# Sheet1.net
KiCad netlist of a schematic drawn in Altium Designer
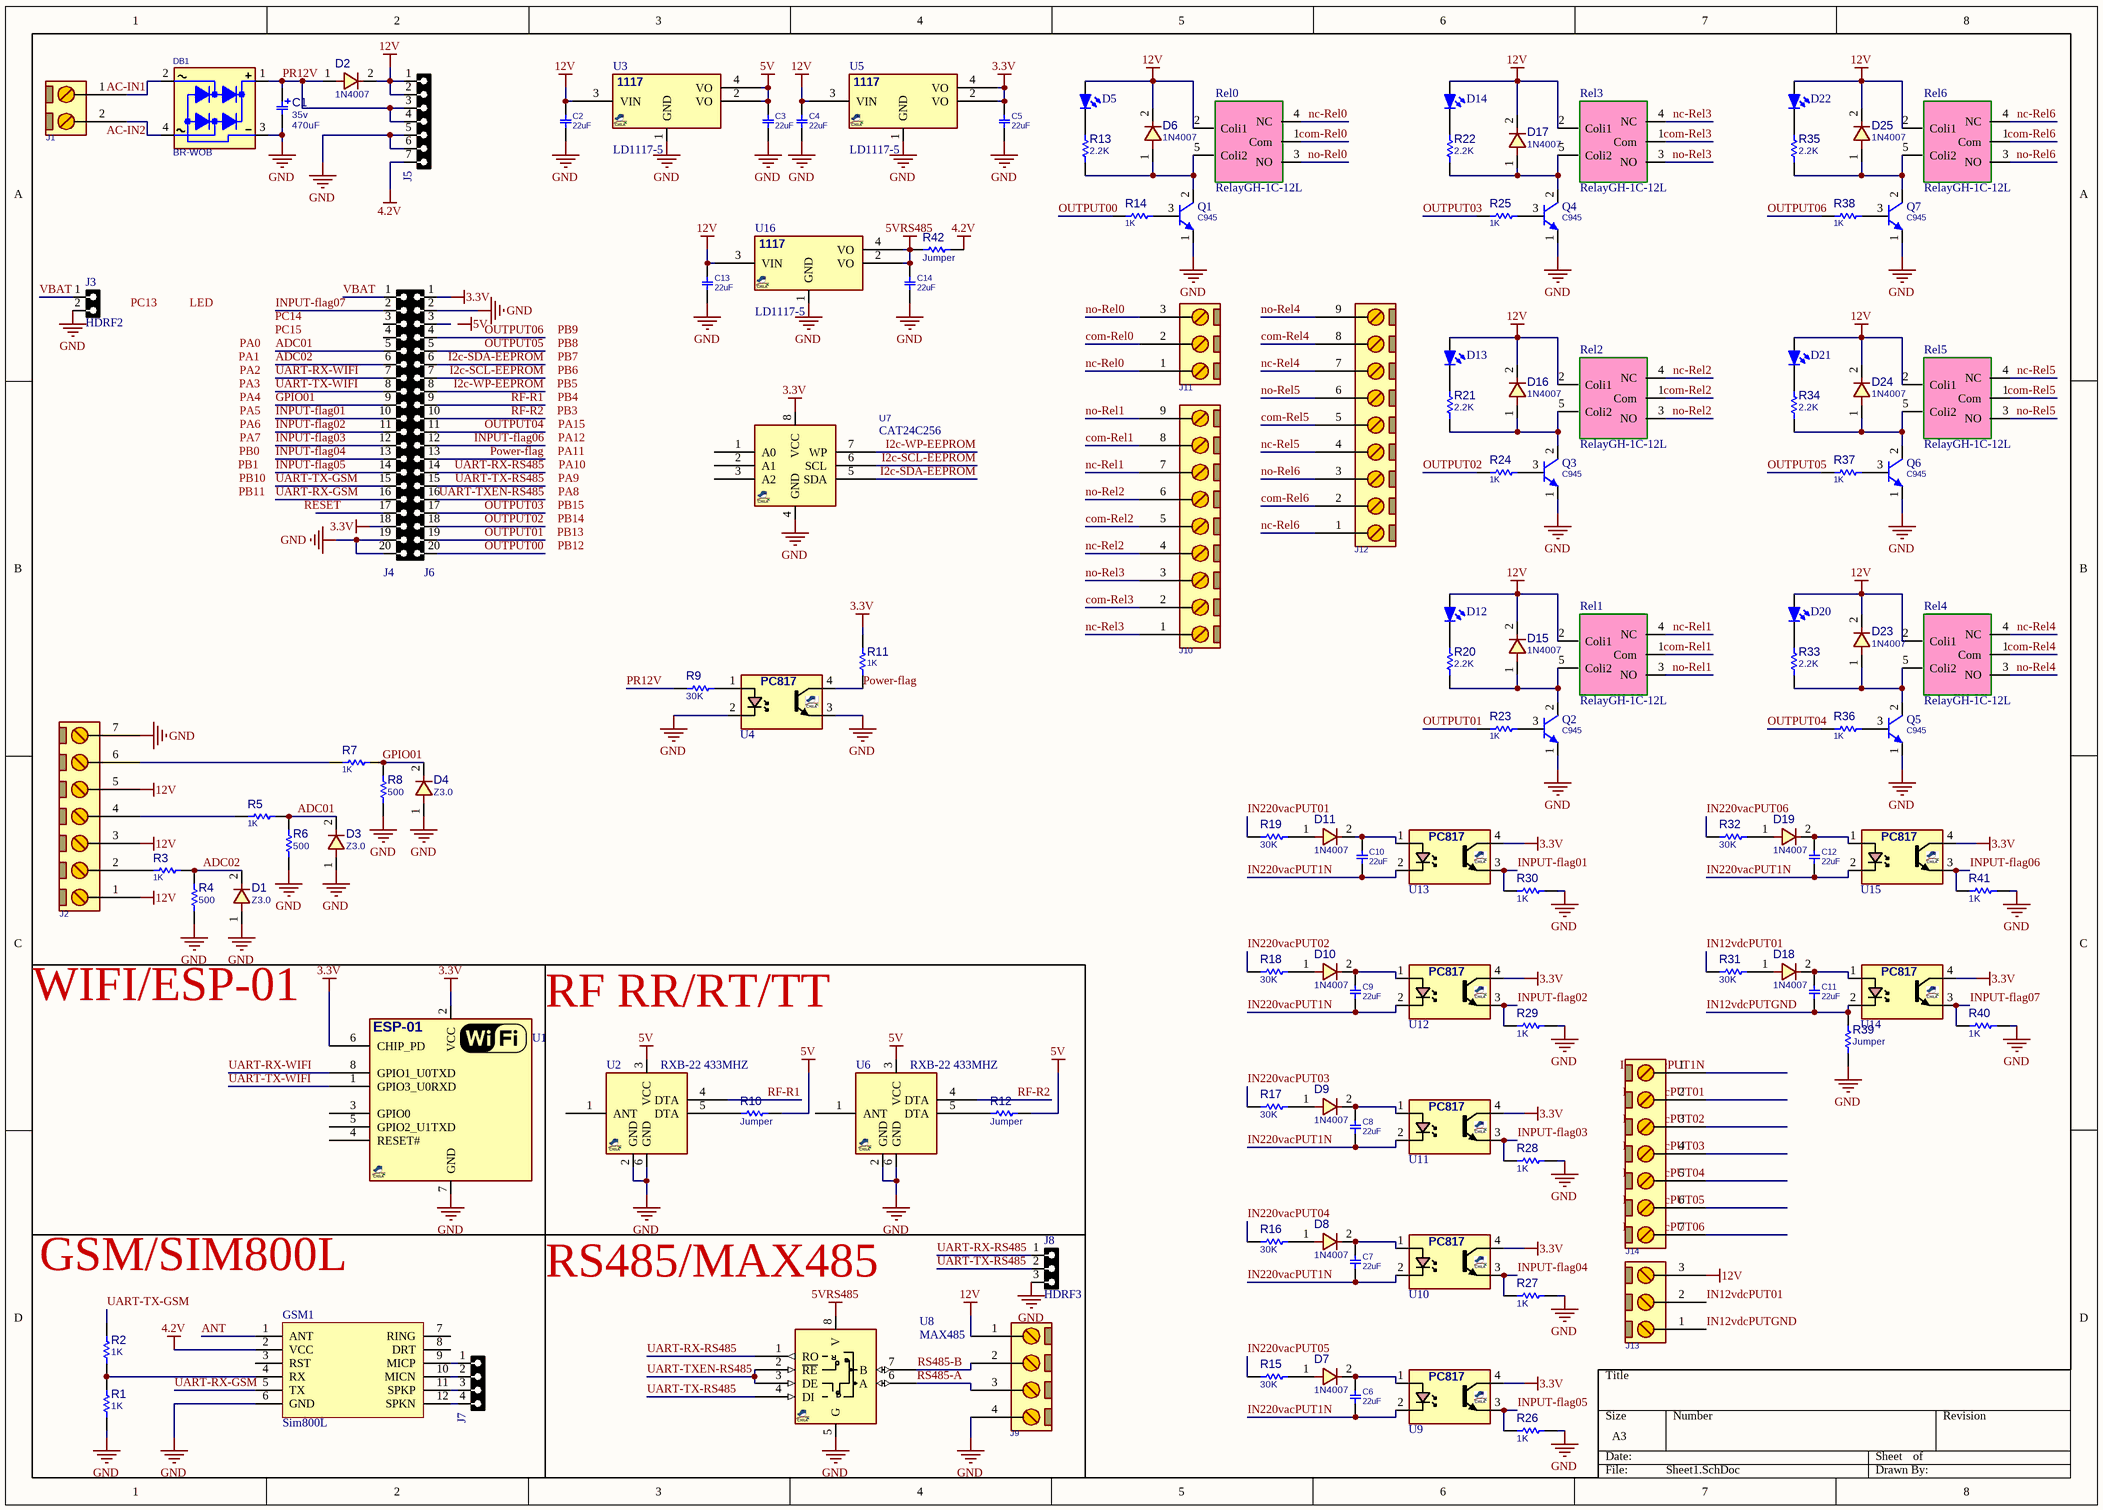
[diagram p0: Sheet1.SchDoc]

(export (version "E")
  (design (tool "Eeschema 10.0.6"))
  (components
    (comp (ref "C1")
      (value "470uF")
      (footprint "C_EL_10X16")
      (description "CAP, THD, ELEC,")
      (fields
        (field (name "MANF_P#") "MANF_PART#")
        (field (name "MANF") "MANF")
        (field (name "PARAM2") "35v")
      )
      (libsource (lib "passive_thd") (part "CAP_THD_EL_470uF_35v"))
    )
    (comp (ref "C2")
      (value "22uF")
      (footprint "C0805")
      (description "CAP, MLCC, X5R 10uF 10% 25V 0805")
      (fields (field (name "MANF_P#") "TMK212BBJ106MG") (field (name "MANF") "Taiyo Yuden"))
      (libsource (lib "mlcc_smd_passive") (part "CAP_SMD_MLCC_10u25V"))
    )
    (comp (ref "C3")
      (value "22uF")
      (footprint "C0805")
      (description "CAP, MLCC, X5R 10uF 10% 25V 0805")
      (fields (field (name "MANF_P#") "TMK212BBJ106MG") (field (name "MANF") "Taiyo Yuden"))
      (libsource (lib "mlcc_smd_passive") (part "CAP_SMD_MLCC_10u25V"))
    )
    (comp (ref "C4")
      (value "22uF")
      (footprint "C0805")
      (description "CAP, MLCC, X5R 10uF 10% 25V 0805")
      (fields (field (name "MANF_P#") "TMK212BBJ106MG") (field (name "MANF") "Taiyo Yuden"))
      (libsource (lib "mlcc_smd_passive") (part "CAP_SMD_MLCC_10u25V"))
    )
    (comp (ref "C5")
      (value "22uF")
      (footprint "C0805")
      (description "CAP, MLCC, X5R 10uF 10% 25V 0805")
      (fields (field (name "MANF_P#") "TMK212BBJ106MG") (field (name "MANF") "Taiyo Yuden"))
      (libsource (lib "mlcc_smd_passive") (part "CAP_SMD_MLCC_10u25V"))
    )
    (comp (ref "C6")
      (value "22uF")
      (footprint "C0805")
      (description "CAP, MLCC, X5R 10uF 10% 25V 0805")
      (fields (field (name "MANF_P#") "TMK212BBJ106MG") (field (name "MANF") "Taiyo Yuden"))
      (libsource (lib "mlcc_smd_passive") (part "CAP_SMD_MLCC_10u25V"))
    )
    (comp (ref "C7")
      (value "22uF")
      (footprint "C0805")
      (description "CAP, MLCC, X5R 10uF 10% 25V 0805")
      (fields (field (name "MANF_P#") "TMK212BBJ106MG") (field (name "MANF") "Taiyo Yuden"))
      (libsource (lib "mlcc_smd_passive") (part "CAP_SMD_MLCC_10u25V"))
    )
    (comp (ref "C8")
      (value "22uF")
      (footprint "C0805")
      (description "CAP, MLCC, X5R 10uF 10% 25V 0805")
      (fields (field (name "MANF_P#") "TMK212BBJ106MG") (field (name "MANF") "Taiyo Yuden"))
      (libsource (lib "mlcc_smd_passive") (part "CAP_SMD_MLCC_10u25V"))
    )
    (comp (ref "C9")
      (value "22uF")
      (footprint "C0805")
      (description "CAP, MLCC, X5R 10uF 10% 25V 0805")
      (fields (field (name "MANF_P#") "TMK212BBJ106MG") (field (name "MANF") "Taiyo Yuden"))
      (libsource (lib "mlcc_smd_passive") (part "CAP_SMD_MLCC_10u25V"))
    )
    (comp (ref "C10")
      (value "22uF")
      (footprint "C0805")
      (description "CAP, MLCC, X5R 10uF 10% 25V 0805")
      (fields (field (name "MANF_P#") "TMK212BBJ106MG") (field (name "MANF") "Taiyo Yuden"))
      (libsource (lib "mlcc_smd_passive") (part "CAP_SMD_MLCC_10u25V"))
    )
    (comp (ref "C11")
      (value "22uF")
      (footprint "C0805")
      (description "CAP, MLCC, X5R 10uF 10% 25V 0805")
      (fields (field (name "MANF_P#") "TMK212BBJ106MG") (field (name "MANF") "Taiyo Yuden"))
      (libsource (lib "mlcc_smd_passive") (part "CAP_SMD_MLCC_10u25V"))
    )
    (comp (ref "C12")
      (value "22uF")
      (footprint "C0805")
      (description "CAP, MLCC, X5R 10uF 10% 25V 0805")
      (fields (field (name "MANF_P#") "TMK212BBJ106MG") (field (name "MANF") "Taiyo Yuden"))
      (libsource (lib "mlcc_smd_passive") (part "CAP_SMD_MLCC_10u25V"))
    )
    (comp (ref "C13")
      (value "22uF")
      (footprint "C0805")
      (description "CAP, MLCC, X5R 10uF 10% 25V 0805")
      (fields (field (name "MANF_P#") "TMK212BBJ106MG") (field (name "MANF") "Taiyo Yuden"))
      (libsource (lib "mlcc_smd_passive") (part "CAP_SMD_MLCC_10u25V"))
    )
    (comp (ref "C14")
      (value "22uF")
      (footprint "C0805")
      (description "CAP, MLCC, X5R 10uF 10% 25V 0805")
      (fields (field (name "MANF_P#") "TMK212BBJ106MG") (field (name "MANF") "Taiyo Yuden"))
      (libsource (lib "mlcc_smd_passive") (part "CAP_SMD_MLCC_10u25V"))
    )
    (comp (ref "D1")
      (value "Z3.0")
      (footprint "D_SOD80")
      (description "DIODE, FAST SWTICHING, 0.3A, 0.5W")
      (fields (field (name "MANF") "MANF") (field (name "MANF_P#") "1N4148"))
      (libsource (lib "altium-import") (part "root_1_DIODE_SMD_1N4148_SOD80_"))
    )
    (comp (ref "D2")
      (value "1N4007")
      (footprint "D_SMA")
      (description "DIODE, GENERAL PURPOSE, 1000V/1A")
      (fields (field (name "MANF") "Kingtronics") (field (name "MANF_P#") "M7"))
      (libsource (lib "diode") (part "DIODE_SMD_1N4007"))
    )
    (comp (ref "D3")
      (value "Z3.0")
      (footprint "D_SOD80")
      (description "DIODE, FAST SWTICHING, 0.3A, 0.5W")
      (fields (field (name "MANF") "MANF") (field (name "MANF_P#") "1N4148"))
      (libsource (lib "altium-import") (part "root_1_DIODE_SMD_1N4148_SOD80_"))
    )
    (comp (ref "D4")
      (value "Z3.0")
      (footprint "D_SOD80")
      (description "DIODE, FAST SWTICHING, 0.3A, 0.5W")
      (fields (field (name "MANF") "MANF") (field (name "MANF_P#") "1N4148"))
      (libsource (lib "altium-import") (part "root_1_DIODE_SMD_1N4148_SOD80_"))
    )
    (comp (ref "D5")
      (value "~")
      (footprint "0805 LED")
      (description "Led")
      (fields (field (name "PUBLISHER") "Altium Limited"))
      (libsource (lib "Sajad_Altium_Library") (part "LED"))
    )
    (comp (ref "D6")
      (value "1N4007")
      (footprint "D_SMA")
      (description "DIODE, GENERAL PURPOSE, 1000V/1A")
      (fields (field (name "MANF") "Kingtronics") (field (name "MANF_P#") "M7"))
      (libsource (lib "diode") (part "DIODE_SMD_1N4007"))
    )
    (comp (ref "D7")
      (value "1N4007")
      (footprint "D_SMA")
      (description "DIODE, GENERAL PURPOSE, 1000V/1A")
      (fields (field (name "MANF") "Kingtronics") (field (name "MANF_P#") "M7"))
      (libsource (lib "diode") (part "DIODE_SMD_1N4007"))
    )
    (comp (ref "D8")
      (value "1N4007")
      (footprint "D_SMA")
      (description "DIODE, GENERAL PURPOSE, 1000V/1A")
      (fields (field (name "MANF") "Kingtronics") (field (name "MANF_P#") "M7"))
      (libsource (lib "diode") (part "DIODE_SMD_1N4007"))
    )
    (comp (ref "D9")
      (value "1N4007")
      (footprint "D_SMA")
      (description "DIODE, GENERAL PURPOSE, 1000V/1A")
      (fields (field (name "MANF") "Kingtronics") (field (name "MANF_P#") "M7"))
      (libsource (lib "diode") (part "DIODE_SMD_1N4007"))
    )
    (comp (ref "D10")
      (value "1N4007")
      (footprint "D_SMA")
      (description "DIODE, GENERAL PURPOSE, 1000V/1A")
      (fields (field (name "MANF") "Kingtronics") (field (name "MANF_P#") "M7"))
      (libsource (lib "diode") (part "DIODE_SMD_1N4007"))
    )
    (comp (ref "D11")
      (value "1N4007")
      (footprint "D_SMA")
      (description "DIODE, GENERAL PURPOSE, 1000V/1A")
      (fields (field (name "MANF") "Kingtronics") (field (name "MANF_P#") "M7"))
      (libsource (lib "diode") (part "DIODE_SMD_1N4007"))
    )
    (comp (ref "D12")
      (value "~")
      (footprint "0805 LED")
      (description "Led")
      (fields (field (name "PUBLISHER") "Altium Limited"))
      (libsource (lib "Sajad_Altium_Library") (part "LED"))
    )
    (comp (ref "D13")
      (value "~")
      (footprint "0805 LED")
      (description "Led")
      (fields (field (name "PUBLISHER") "Altium Limited"))
      (libsource (lib "Sajad_Altium_Library") (part "LED"))
    )
    (comp (ref "D14")
      (value "~")
      (footprint "0805 LED")
      (description "Led")
      (fields (field (name "PUBLISHER") "Altium Limited"))
      (libsource (lib "Sajad_Altium_Library") (part "LED"))
    )
    (comp (ref "D15")
      (value "1N4007")
      (footprint "D_SMA")
      (description "DIODE, GENERAL PURPOSE, 1000V/1A")
      (fields (field (name "MANF") "Kingtronics") (field (name "MANF_P#") "M7"))
      (libsource (lib "diode") (part "DIODE_SMD_1N4007"))
    )
    (comp (ref "D16")
      (value "1N4007")
      (footprint "D_SMA")
      (description "DIODE, GENERAL PURPOSE, 1000V/1A")
      (fields (field (name "MANF") "Kingtronics") (field (name "MANF_P#") "M7"))
      (libsource (lib "diode") (part "DIODE_SMD_1N4007"))
    )
    (comp (ref "D17")
      (value "1N4007")
      (footprint "D_SMA")
      (description "DIODE, GENERAL PURPOSE, 1000V/1A")
      (fields (field (name "MANF") "Kingtronics") (field (name "MANF_P#") "M7"))
      (libsource (lib "diode") (part "DIODE_SMD_1N4007"))
    )
    (comp (ref "D18")
      (value "1N4007")
      (footprint "D_SMA")
      (description "DIODE, GENERAL PURPOSE, 1000V/1A")
      (fields (field (name "MANF") "Kingtronics") (field (name "MANF_P#") "M7"))
      (libsource (lib "diode") (part "DIODE_SMD_1N4007"))
    )
    (comp (ref "D19")
      (value "1N4007")
      (footprint "D_SMA")
      (description "DIODE, GENERAL PURPOSE, 1000V/1A")
      (fields (field (name "MANF") "Kingtronics") (field (name "MANF_P#") "M7"))
      (libsource (lib "diode") (part "DIODE_SMD_1N4007"))
    )
    (comp (ref "D20")
      (value "~")
      (footprint "0805 LED")
      (description "Led")
      (fields (field (name "PUBLISHER") "Altium Limited"))
      (libsource (lib "Sajad_Altium_Library") (part "LED"))
    )
    (comp (ref "D21")
      (value "~")
      (footprint "0805 LED")
      (description "Led")
      (fields (field (name "PUBLISHER") "Altium Limited"))
      (libsource (lib "Sajad_Altium_Library") (part "LED"))
    )
    (comp (ref "D22")
      (value "~")
      (footprint "0805 LED")
      (description "Led")
      (fields (field (name "PUBLISHER") "Altium Limited"))
      (libsource (lib "Sajad_Altium_Library") (part "LED"))
    )
    (comp (ref "D23")
      (value "1N4007")
      (footprint "D_SMA")
      (description "DIODE, GENERAL PURPOSE, 1000V/1A")
      (fields (field (name "MANF") "Kingtronics") (field (name "MANF_P#") "M7"))
      (libsource (lib "diode") (part "DIODE_SMD_1N4007"))
    )
    (comp (ref "D24")
      (value "1N4007")
      (footprint "D_SMA")
      (description "DIODE, GENERAL PURPOSE, 1000V/1A")
      (fields (field (name "MANF") "Kingtronics") (field (name "MANF_P#") "M7"))
      (libsource (lib "diode") (part "DIODE_SMD_1N4007"))
    )
    (comp (ref "D25")
      (value "1N4007")
      (footprint "D_SMA")
      (description "DIODE, GENERAL PURPOSE, 1000V/1A")
      (fields (field (name "MANF") "Kingtronics") (field (name "MANF_P#") "M7"))
      (libsource (lib "diode") (part "DIODE_SMD_1N4007"))
    )
    (comp (ref "DB1")
      (value "BR-WOB")
      (footprint "DBRG_C10")
      (description "DIODE, BRIDGE,")
      (libsource (lib "diode") (part "DIODE_THD_BRIDGE_WO"))
    )
    (comp (ref "GSM1")
      (value "Sim800L")
      (footprint "Sim800L")
      (libsource (lib "Sim800L_Module") (part "Sim800L"))
    )
    (comp (ref "J1")
      (value "CONN_TB2")
      (footprint "MSTB_2")
      (description "CONN, PHOENIX MSTB, 5-G, 5.08mm pitch")
      (libsource (lib "conn_terminalB") (part "CONN_MSTB_2"))
    )
    (comp (ref "J2")
      (value "CONN_TB7")
      (footprint "MSTB_7")
      (description "CONN, PHOENIX MSTB, 5-G, 5.08mm pitch")
      (libsource (lib "altium-import") (part "root_2_CONN_MSTB_7_"))
    )
    (comp (ref "J3")
      (value "HDRF2")
      (footprint "HDR_F_1X2")
      (description "CONN, HEADER, Female, pitch: 2.54mm, 2POS")
      (libsource (lib "altium-import") (part "root_0_HDR_F_1X2_"))
    )
    (comp (ref "J4")
      (value "HDRF20")
      (footprint "HDR_F_1X20")
      (description "CONN, HEADER, Female, pitch: 2.54mm, 20POS")
      (libsource (lib "conn_header_2.54_st") (part "HDR_F_1X20"))
    )
    (comp (ref "J5")
      (value "HDRF7")
      (footprint "HDR_F_1X7")
      (description "CONN, HEADER, Female, pitch: 2.54mm, 7POS")
      (libsource (lib "altium-import") (part "root_0_HDR_F_1X7_"))
    )
    (comp (ref "J6")
      (value "HDRF20")
      (footprint "HDR_F_1X20")
      (description "CONN, HEADER, Female, pitch: 2.54mm, 20POS")
      (libsource (lib "conn_header_2.54_st") (part "HDR_F_1X20"))
    )
    (comp (ref "J7")
      (value "HDRF4")
      (footprint "HDR_F_1X4")
      (description "CONN, HEADER, Female, pitch: 2.54mm, 4POS")
      (libsource (lib "conn_header_2.54_st") (part "HDR_F_1X4"))
    )
    (comp (ref "J8")
      (value "HDRF3")
      (footprint "HDR_F_1X3")
      (description "CONN, HEADER, Female, pitch: 2.54mm, 3POS")
      (libsource (lib "conn_header_2.54mm_st") (part "HDR_F_1X3"))
    )
    (comp (ref "J9")
      (value "CONN_TB4")
      (footprint "MSTB_4")
      (description "CONN, PHOENIX MSTB, 5-G, 5.08mm pitch")
      (libsource (lib "altium-import") (part "root_0_CONN_MSTB_4_"))
    )
    (comp (ref "J10")
      (value "CONN_TB9")
      (footprint "MSTB_9")
      (description "CONN, PHOENIX MSTB, 5-G, 5.08mm pitch")
      (libsource (lib "conn_terminalB") (part "CONN_MSTB_9"))
    )
    (comp (ref "J11")
      (value "CONN_TB3")
      (footprint "MSTB_3")
      (description "CONN, PHOENIX MSTB, 5-G, 5.08mm pitch")
      (libsource (lib "conn_terminalB") (part "CONN_MSTB_3"))
    )
    (comp (ref "J12")
      (value "CONN_TB9")
      (footprint "MSTB_9")
      (description "CONN, PHOENIX MSTB, 5-G, 5.08mm pitch")
      (libsource (lib "conn_terminalB") (part "CONN_MSTB_9"))
    )
    (comp (ref "J13")
      (value "CONN_TB3")
      (footprint "MSTB_3")
      (description "CONN, PHOENIX MSTB, 5-G, 5.08mm pitch")
      (libsource (lib "") (part "CONN_MSTB_3_1"))
    )
    (comp (ref "J14")
      (value "CONN_TB7")
      (footprint "MSTB_7")
      (description "CONN, PHOENIX MSTB, 5-G, 5.08mm pitch")
      (libsource (lib "altium-import") (part "root_0_mirrored_CONN_MSTB_7_"))
    )
    (comp (ref "Q1")
      (value "C945")
      (footprint "TO92_3")
      (description "BJT, NPN, 50v, 0.15A, THD, TO92, BC945")
      (fields (field (name "MANF_P#") "C945, 2SC945, BC945"))
      (libsource (lib "transistor_bjt") (part "NPN_C945_TO92"))
    )
    (comp (ref "Q2")
      (value "C945")
      (footprint "TO92_3")
      (description "BJT, NPN, 50v, 0.15A, THD, TO92, BC945")
      (fields (field (name "MANF_P#") "C945, 2SC945, BC945"))
      (libsource (lib "transistor_bjt") (part "NPN_C945_TO92"))
    )
    (comp (ref "Q3")
      (value "C945")
      (footprint "TO92_3")
      (description "BJT, NPN, 50v, 0.15A, THD, TO92, BC945")
      (fields (field (name "MANF_P#") "C945, 2SC945, BC945"))
      (libsource (lib "transistor_bjt") (part "NPN_C945_TO92"))
    )
    (comp (ref "Q4")
      (value "C945")
      (footprint "TO92_3")
      (description "BJT, NPN, 50v, 0.15A, THD, TO92, BC945")
      (fields (field (name "MANF_P#") "C945, 2SC945, BC945"))
      (libsource (lib "transistor_bjt") (part "NPN_C945_TO92"))
    )
    (comp (ref "Q5")
      (value "C945")
      (footprint "TO92_3")
      (description "BJT, NPN, 50v, 0.15A, THD, TO92, BC945")
      (fields (field (name "MANF_P#") "C945, 2SC945, BC945"))
      (libsource (lib "transistor_bjt") (part "NPN_C945_TO92"))
    )
    (comp (ref "Q6")
      (value "C945")
      (footprint "TO92_3")
      (description "BJT, NPN, 50v, 0.15A, THD, TO92, BC945")
      (fields (field (name "MANF_P#") "C945, 2SC945, BC945"))
      (libsource (lib "transistor_bjt") (part "NPN_C945_TO92"))
    )
    (comp (ref "Q7")
      (value "C945")
      (footprint "TO92_3")
      (description "BJT, NPN, 50v, 0.15A, THD, TO92, BC945")
      (fields (field (name "MANF_P#") "C945, 2SC945, BC945"))
      (libsource (lib "transistor_bjt") (part "NPN_C945_TO92"))
    )
    (comp (ref "R1")
      (value "1K")
      (footprint "R0805")
      (description "RESISTOR, SMD")
      (libsource (lib "passive_smd") (part "RES_SMD_0805"))
    )
    (comp (ref "R2")
      (value "1K")
      (footprint "R0805")
      (description "RESISTOR, SMD")
      (libsource (lib "passive_smd") (part "RES_SMD_0805"))
    )
    (comp (ref "R3")
      (value "1K")
      (footprint "R025W_AX04")
      (description "RESISTOR, THD")
      (fields (field (name "MANF_P#") "RK73H1ETTP4701F") (field (name "MANF") "KOA SPEER"))
      (libsource (lib "passive_thd") (part "RES_THD"))
    )
    (comp (ref "R4")
      (value "500")
      (footprint "R0805")
      (description "RESISTOR, SMD")
      (libsource (lib "passive_smd") (part "RES_SMD_0805"))
    )
    (comp (ref "R5")
      (value "1K")
      (footprint "R025W_AX04")
      (description "RESISTOR, THD")
      (fields (field (name "MANF_P#") "RK73H1ETTP4701F") (field (name "MANF") "KOA SPEER"))
      (libsource (lib "passive_thd") (part "RES_THD"))
    )
    (comp (ref "R6")
      (value "500")
      (footprint "R0805")
      (description "RESISTOR, SMD")
      (libsource (lib "passive_smd") (part "RES_SMD_0805"))
    )
    (comp (ref "R7")
      (value "1K")
      (footprint "R025W_AX04")
      (description "RESISTOR, THD")
      (fields (field (name "MANF_P#") "RK73H1ETTP4701F") (field (name "MANF") "KOA SPEER"))
      (libsource (lib "passive_thd") (part "RES_THD"))
    )
    (comp (ref "R8")
      (value "500")
      (footprint "R0805")
      (description "RESISTOR, SMD")
      (libsource (lib "passive_smd") (part "RES_SMD_0805"))
    )
    (comp (ref "R9")
      (value "30K")
      (footprint "R0805")
      (description "RESISTOR, SMD")
      (libsource (lib "passive_smd") (part "RES_SMD"))
    )
    (comp (ref "R10")
      (value "Jumper")
      (footprint "R0805")
      (description "RESISTOR, SMD")
      (libsource (lib "passive_smd") (part "RES_SMD_0805"))
    )
    (comp (ref "R11")
      (value "1K")
      (footprint "R025W_AX04")
      (description "RESISTOR, THD")
      (fields (field (name "MANF_P#") "RK73H1ETTP4701F") (field (name "MANF") "KOA SPEER"))
      (libsource (lib "passive_thd") (part "RES_THD"))
    )
    (comp (ref "R12")
      (value "Jumper")
      (footprint "R0805")
      (description "RESISTOR, SMD")
      (libsource (lib "passive_smd") (part "RES_SMD_0805"))
    )
    (comp (ref "R13")
      (value "2.2K")
      (footprint "R0805")
      (description "RESISTOR, SMD")
      (libsource (lib "passive_smd") (part "RES_SMD"))
    )
    (comp (ref "R14")
      (value "1K")
      (footprint "R025W_AX04")
      (description "RESISTOR, THD")
      (fields (field (name "MANF_P#") "RK73H1ETTP4701F") (field (name "MANF") "KOA SPEER"))
      (libsource (lib "passive_thd") (part "RES_THD"))
    )
    (comp (ref "R15")
      (value "30K")
      (footprint "R0805")
      (description "RESISTOR, SMD")
      (libsource (lib "passive_smd") (part "RES_SMD"))
    )
    (comp (ref "R16")
      (value "30K")
      (footprint "R0805")
      (description "RESISTOR, SMD")
      (libsource (lib "passive_smd") (part "RES_SMD"))
    )
    (comp (ref "R17")
      (value "30K")
      (footprint "R0805")
      (description "RESISTOR, SMD")
      (libsource (lib "passive_smd") (part "RES_SMD"))
    )
    (comp (ref "R18")
      (value "30K")
      (footprint "R0805")
      (description "RESISTOR, SMD")
      (libsource (lib "passive_smd") (part "RES_SMD"))
    )
    (comp (ref "R19")
      (value "30K")
      (footprint "R0805")
      (description "RESISTOR, SMD")
      (libsource (lib "passive_smd") (part "RES_SMD_0805"))
    )
    (comp (ref "R20")
      (value "2.2K")
      (footprint "R0805")
      (description "RESISTOR, SMD")
      (libsource (lib "passive_smd") (part "RES_SMD"))
    )
    (comp (ref "R21")
      (value "2.2K")
      (footprint "R0805")
      (description "RESISTOR, SMD")
      (libsource (lib "passive_smd") (part "RES_SMD"))
    )
    (comp (ref "R22")
      (value "2.2K")
      (footprint "R0805")
      (description "RESISTOR, SMD")
      (libsource (lib "passive_smd") (part "RES_SMD"))
    )
    (comp (ref "R23")
      (value "1K")
      (footprint "R025W_AX04")
      (description "RESISTOR, THD")
      (fields (field (name "MANF_P#") "RK73H1ETTP4701F") (field (name "MANF") "KOA SPEER"))
      (libsource (lib "passive_thd") (part "RES_THD"))
    )
    (comp (ref "R24")
      (value "1K")
      (footprint "R025W_AX04")
      (description "RESISTOR, THD")
      (fields (field (name "MANF_P#") "RK73H1ETTP4701F") (field (name "MANF") "KOA SPEER"))
      (libsource (lib "passive_thd") (part "RES_THD"))
    )
    (comp (ref "R25")
      (value "1K")
      (footprint "R025W_AX04")
      (description "RESISTOR, THD")
      (fields (field (name "MANF_P#") "RK73H1ETTP4701F") (field (name "MANF") "KOA SPEER"))
      (libsource (lib "passive_thd") (part "RES_THD"))
    )
    (comp (ref "R26")
      (value "1K")
      (footprint "R0805")
      (description "RESISTOR, SMD")
      (libsource (lib "passive_smd") (part "RES_SMD"))
    )
    (comp (ref "R27")
      (value "1K")
      (footprint "R0805")
      (description "RESISTOR, SMD")
      (libsource (lib "passive_smd") (part "RES_SMD"))
    )
    (comp (ref "R28")
      (value "1K")
      (footprint "R0805")
      (description "RESISTOR, SMD")
      (libsource (lib "passive_smd") (part "RES_SMD"))
    )
    (comp (ref "R29")
      (value "1K")
      (footprint "R0805")
      (description "RESISTOR, SMD")
      (libsource (lib "passive_smd") (part "RES_SMD"))
    )
    (comp (ref "R30")
      (value "1K")
      (footprint "R0805")
      (description "RESISTOR, SMD")
      (libsource (lib "passive_smd") (part "RES_SMD"))
    )
    (comp (ref "R31")
      (value "30K")
      (footprint "R0805")
      (description "RESISTOR, SMD")
      (libsource (lib "passive_smd") (part "RES_SMD"))
    )
    (comp (ref "R32")
      (value "30K")
      (footprint "R0805")
      (description "RESISTOR, SMD")
      (libsource (lib "passive_smd") (part "RES_SMD"))
    )
    (comp (ref "R33")
      (value "2.2K")
      (footprint "R0805")
      (description "RESISTOR, SMD")
      (libsource (lib "passive_smd") (part "RES_SMD"))
    )
    (comp (ref "R34")
      (value "2.2K")
      (footprint "R0805")
      (description "RESISTOR, SMD")
      (libsource (lib "passive_smd") (part "RES_SMD"))
    )
    (comp (ref "R35")
      (value "2.2K")
      (footprint "R0805")
      (description "RESISTOR, SMD")
      (libsource (lib "passive_smd") (part "RES_SMD"))
    )
    (comp (ref "R36")
      (value "1K")
      (footprint "R025W_AX04")
      (description "RESISTOR, THD")
      (fields (field (name "MANF_P#") "RK73H1ETTP4701F") (field (name "MANF") "KOA SPEER"))
      (libsource (lib "passive_thd") (part "RES_THD"))
    )
    (comp (ref "R37")
      (value "1K")
      (footprint "R025W_AX04")
      (description "RESISTOR, THD")
      (fields (field (name "MANF_P#") "RK73H1ETTP4701F") (field (name "MANF") "KOA SPEER"))
      (libsource (lib "passive_thd") (part "RES_THD"))
    )
    (comp (ref "R38")
      (value "1K")
      (footprint "R025W_AX04")
      (description "RESISTOR, THD")
      (fields (field (name "MANF_P#") "RK73H1ETTP4701F") (field (name "MANF") "KOA SPEER"))
      (libsource (lib "passive_thd") (part "RES_THD"))
    )
    (comp (ref "R39")
      (value "Jumper")
      (footprint "R0805")
      (description "RESISTOR, SMD")
      (libsource (lib "passive_smd") (part "RES_SMD"))
    )
    (comp (ref "R40")
      (value "1K")
      (footprint "R0805")
      (description "RESISTOR, SMD")
      (libsource (lib "passive_smd") (part "RES_SMD"))
    )
    (comp (ref "R41")
      (value "1K")
      (footprint "R0805")
      (description "RESISTOR, SMD")
      (libsource (lib "passive_smd") (part "RES_SMD"))
    )
    (comp (ref "R42")
      (value "Jumper")
      (footprint "R0805")
      (description "RESISTOR, SMD")
      (libsource (lib "passive_smd") (part "RES_SMD_0805"))
    )
    (comp (ref "Rel0")
      (value "RelayGH-1C-12L")
      (footprint "GH-1C-12L")
      (description "HJR-3FF-12VDC-S-Z")
      (libsource (lib "Sajad_Altium_Library") (part "RelayGH-1C-12L"))
    )
    (comp (ref "Rel1")
      (value "RelayGH-1C-12L")
      (footprint "GH-1C-12L")
      (description "HJR-3FF-12VDC-S-Z")
      (libsource (lib "Sajad_Altium_Library") (part "RelayGH-1C-12L"))
    )
    (comp (ref "Rel2")
      (value "RelayGH-1C-12L")
      (footprint "GH-1C-12L")
      (description "HJR-3FF-12VDC-S-Z")
      (libsource (lib "Sajad_Altium_Library") (part "RelayGH-1C-12L"))
    )
    (comp (ref "Rel3")
      (value "RelayGH-1C-12L")
      (footprint "GH-1C-12L")
      (description "HJR-3FF-12VDC-S-Z")
      (libsource (lib "Sajad_Altium_Library") (part "RelayGH-1C-12L"))
    )
    (comp (ref "Rel4")
      (value "RelayGH-1C-12L")
      (footprint "GH-1C-12L")
      (description "HJR-3FF-12VDC-S-Z")
      (libsource (lib "Sajad_Altium_Library") (part "RelayGH-1C-12L"))
    )
    (comp (ref "Rel5")
      (value "RelayGH-1C-12L")
      (footprint "GH-1C-12L")
      (description "HJR-3FF-12VDC-S-Z")
      (libsource (lib "Sajad_Altium_Library") (part "RelayGH-1C-12L"))
    )
    (comp (ref "Rel6")
      (value "RelayGH-1C-12L")
      (footprint "GH-1C-12L")
      (description "HJR-3FF-12VDC-S-Z")
      (libsource (lib "Sajad_Altium_Library") (part "RelayGH-1C-12L"))
    )
    (comp (ref "U1")
      (value "ESP-01")
      (footprint "ESP8266_ESP01")
      (description "ESP8266 ESP-01 WiFi Module")
      (libsource (lib "module_wifi") (part "ESP8266_ESP-01"))
    )
    (comp (ref "U2")
      (value "RXB-22 433MHZ")
      (footprint "RF_ETRXB")
      (description "Modules RF 433MHz")
      (fields (field (name "MANF") "www.eeant.com") (field (name "MANF_P#") "ET-RXB-22"))
      (libsource (lib "altium-import") (part "root_0_ET-RXB-22_"))
    )
    (comp (ref "U3")
      (value "LD1117-5")
      (footprint "SOT223_4")
      (description "REG, Linear, LDO1V, 0.8A, SOT-223")
      (fields
        (field (name "MANF_P#") "LD1117, LM1117, AMS1117, TLV1117, REG1117, NCP1117, LT1117, SPX1117")
        (field (name "MANF") "TI, ON, ST")
      )
      (libsource (lib "pwr_reg_linear_1117") (part "VREG_1117_SOT223"))
    )
    (comp (ref "U4")
      (value "PC817")
      (footprint "DIP_4")
      (description "OPTOCOUPLER, TRANSISTOR, 4PIN")
      (fields (field (name "MANF") "SHARP"))
      (libsource (lib "optocoupler") (part "OPTC_TR4P_PC817"))
    )
    (comp (ref "U5")
      (value "LD1117-5")
      (footprint "SOT223_4")
      (description "REG, Linear, LDO1V, 0.8A, SOT-223")
      (fields
        (field (name "MANF_P#") "LD1117, LM1117, AMS1117, TLV1117, REG1117, NCP1117, LT1117, SPX1117")
        (field (name "MANF") "TI, ON, ST")
      )
      (libsource (lib "pwr_reg_linear_1117") (part "VREG_1117_SOT223"))
    )
    (comp (ref "U6")
      (value "RXB-22 433MHZ")
      (footprint "RF_ETRXB")
      (description "Modules RF 433MHz")
      (fields (field (name "MANF") "www.eeant.com") (field (name "MANF_P#") "ET-RXB-22"))
      (libsource (lib "altium-import") (part "root_0_ET-RXB-22_"))
    )
    (comp (ref "U7")
      (value "CAT24C256")
      (footprint "SO_8")
      (description "EEPROM, I2C, 256Kb,  SOP-8")
      (fields (field (name "MANF") "ON") (field (name "MANF_P#") "CAT24C256W"))
      (libsource (lib "altium-import") (part "root_0_EEPROM_I2C_CAT24C256_SOP8_"))
    )
    (comp (ref "U8")
      (value "MAX485")
      (footprint "DIP_8")
      (description "RS-485 Transceiver, 5V, DIP-8, ±7V Ground Difference Between Devices on the Bus")
      (fields (field (name "MANF_P#") "MAX485EPA") (field (name "MANF") "Maxim Integrated"))
      (libsource (lib "rs485-422") (part "MAX485_DIP8"))
    )
    (comp (ref "U9")
      (value "PC817")
      (footprint "DIP_4")
      (description "OPTOCOUPLER, TRANSISTOR, 4PIN")
      (fields (field (name "MANF") "SHARP"))
      (libsource (lib "optocoupler") (part "OPTC_TR4P_PC817"))
    )
    (comp (ref "U10")
      (value "PC817")
      (footprint "DIP_4")
      (description "OPTOCOUPLER, TRANSISTOR, 4PIN")
      (fields (field (name "MANF") "SHARP"))
      (libsource (lib "optocoupler") (part "OPTC_TR4P_PC817"))
    )
    (comp (ref "U11")
      (value "PC817")
      (footprint "DIP_4")
      (description "OPTOCOUPLER, TRANSISTOR, 4PIN")
      (fields (field (name "MANF") "SHARP"))
      (libsource (lib "optocoupler") (part "OPTC_TR4P_PC817"))
    )
    (comp (ref "U12")
      (value "PC817")
      (footprint "DIP_4")
      (description "OPTOCOUPLER, TRANSISTOR, 4PIN")
      (fields (field (name "MANF") "SHARP"))
      (libsource (lib "optocoupler") (part "OPTC_TR4P_PC817"))
    )
    (comp (ref "U13")
      (value "PC817")
      (footprint "DIP_4")
      (description "OPTOCOUPLER, TRANSISTOR, 4PIN")
      (fields (field (name "MANF") "SHARP"))
      (libsource (lib "optocoupler") (part "OPTC_TR4P_PC817"))
    )
    (comp (ref "U14")
      (value "PC817")
      (footprint "DIP_4")
      (description "OPTOCOUPLER, TRANSISTOR, 4PIN")
      (fields (field (name "MANF") "SHARP"))
      (libsource (lib "optocoupler") (part "OPTC_TR4P_PC817"))
    )
    (comp (ref "U15")
      (value "PC817")
      (footprint "DIP_4")
      (description "OPTOCOUPLER, TRANSISTOR, 4PIN")
      (fields (field (name "MANF") "SHARP"))
      (libsource (lib "optocoupler") (part "OPTC_TR4P_PC817"))
    )
    (comp (ref "U16")
      (value "LD1117-5")
      (footprint "SOT223_4")
      (description "REG, Linear, LDO1V, 0.8A, SOT-223")
      (fields
        (field (name "MANF_P#") "LD1117, LM1117, AMS1117, TLV1117, REG1117, NCP1117, LT1117, SPX1117")
        (field (name "MANF") "TI, ON, ST")
      )
      (libsource (lib "pwr_reg_linear_1117") (part "VREG_1117_SOT223"))
    )
  )
  (nets
    (net (code "1") (name "/AC-IN1") (class "Default")
      (node (ref "DB1") (pin "2") (pinfunction "AC1_2") (pintype "passive"))
      (node (ref "J1") (pin "1") (pinfunction "1_1") (pintype "passive"))
    )
    (net (code "2") (name "/AC-IN2") (class "Default")
      (node (ref "DB1") (pin "4") (pinfunction "AC2_4") (pintype "passive"))
      (node (ref "J1") (pin "2") (pinfunction "2_2") (pintype "passive"))
    )
    (net (code "3") (name "/ADC01") (class "Default")
      (node (ref "D3") (pin "2") (pinfunction "2_2") (pintype "passive"))
      (node (ref "J4") (pin "5") (pinfunction "5_5") (pintype "passive"))
      (node (ref "R5") (pin "2") (pinfunction "2_2") (pintype "passive"))
      (node (ref "R6") (pin "1") (pinfunction "1_1") (pintype "passive"))
    )
    (net (code "4") (name "/ADC02") (class "Default")
      (node (ref "D1") (pin "2") (pinfunction "2_2") (pintype "passive"))
      (node (ref "J4") (pin "6") (pinfunction "6_6") (pintype "passive"))
      (node (ref "R3") (pin "2") (pinfunction "2_2") (pintype "passive"))
      (node (ref "R4") (pin "1") (pinfunction "1_1") (pintype "passive"))
    )
    (net (code "5") (name "/ANT") (class "Default")
      (node (ref "GSM1") (pin "1") (pinfunction "ANT_1") (pintype "passive"))
    )
    (net (code "6") (name "/GPIO01") (class "Default")
      (node (ref "D4") (pin "2") (pinfunction "2_2") (pintype "passive"))
      (node (ref "J4") (pin "9") (pinfunction "9_9") (pintype "passive"))
      (node (ref "R7") (pin "2") (pinfunction "2_2") (pintype "passive"))
      (node (ref "R8") (pin "1") (pinfunction "1_1") (pintype "passive"))
    )
    (net (code "7") (name "/I2c-SCL-EEPROM") (class "Default")
      (node (ref "J6") (pin "7") (pinfunction "7_7") (pintype "passive"))
      (node (ref "U7") (pin "6") (pinfunction "SCL_6") (pintype "passive"))
    )
    (net (code "8") (name "/I2c-SDA-EEPROM") (class "Default")
      (node (ref "J6") (pin "6") (pinfunction "6_6") (pintype "passive"))
      (node (ref "U7") (pin "5") (pinfunction "SDA_5") (pintype "passive"))
    )
    (net (code "9") (name "/I2c-WP-EEPROM") (class "Default")
      (node (ref "J6") (pin "8") (pinfunction "8_8") (pintype "passive"))
      (node (ref "U7") (pin "7") (pinfunction "WP_7") (pintype "passive"))
    )
    (net (code "10") (name "/IN12vdcPUT01") (class "Default")
      (node (ref "J13") (pin "2") (pinfunction "2_2") (pintype "passive"))
      (node (ref "R31") (pin "1") (pinfunction "1_1") (pintype "passive"))
    )
    (net (code "11") (name "/IN12vdcPUTGND") (class "Default")
      (node (ref "C11") (pin "2") (pinfunction "2_2") (pintype "passive"))
      (node (ref "J13") (pin "1") (pinfunction "1_1") (pintype "passive"))
      (node (ref "R39") (pin "1") (pinfunction "1_1") (pintype "passive"))
      (node (ref "U14") (pin "2") (pinfunction "K_2") (pintype "passive"))
    )
    (net (code "12") (name "/IN220vacPUT01") (class "Default")
      (node (ref "J14") (pin "2") (pinfunction "2_2") (pintype "passive"))
      (node (ref "R19") (pin "1") (pinfunction "1_1") (pintype "passive"))
    )
    (net (code "13") (name "/IN220vacPUT1N") (class "Default")
      (node (ref "C10") (pin "2") (pinfunction "2_2") (pintype "passive"))
      (node (ref "C12") (pin "2") (pinfunction "2_2") (pintype "passive"))
      (node (ref "C6") (pin "2") (pinfunction "2_2") (pintype "passive"))
      (node (ref "C7") (pin "2") (pinfunction "2_2") (pintype "passive"))
      (node (ref "C8") (pin "2") (pinfunction "2_2") (pintype "passive"))
      (node (ref "C9") (pin "2") (pinfunction "2_2") (pintype "passive"))
      (node (ref "J14") (pin "1") (pinfunction "1_1") (pintype "passive"))
      (node (ref "U10") (pin "2") (pinfunction "K_2") (pintype "passive"))
      (node (ref "U11") (pin "2") (pinfunction "K_2") (pintype "passive"))
      (node (ref "U12") (pin "2") (pinfunction "K_2") (pintype "passive"))
      (node (ref "U13") (pin "2") (pinfunction "K_2") (pintype "passive"))
      (node (ref "U15") (pin "2") (pinfunction "K_2") (pintype "passive"))
      (node (ref "U9") (pin "2") (pinfunction "K_2") (pintype "passive"))
    )
    (net (code "14") (name "/IN220vacPUT02") (class "Default")
      (node (ref "J14") (pin "3") (pinfunction "3_3") (pintype "passive"))
      (node (ref "R18") (pin "1") (pinfunction "1_1") (pintype "passive"))
    )
    (net (code "15") (name "/IN220vacPUT03") (class "Default")
      (node (ref "J14") (pin "4") (pinfunction "4_4") (pintype "passive"))
      (node (ref "R17") (pin "1") (pinfunction "1_1") (pintype "passive"))
    )
    (net (code "16") (name "/IN220vacPUT04") (class "Default")
      (node (ref "J14") (pin "5") (pinfunction "5_5") (pintype "passive"))
      (node (ref "R16") (pin "1") (pinfunction "1_1") (pintype "passive"))
    )
    (net (code "17") (name "/IN220vacPUT05") (class "Default")
      (node (ref "J14") (pin "6") (pinfunction "6_6") (pintype "passive"))
      (node (ref "R15") (pin "1") (pinfunction "1_1") (pintype "passive"))
    )
    (net (code "18") (name "/IN220vacPUT06") (class "Default")
      (node (ref "J14") (pin "7") (pinfunction "7_7") (pintype "passive"))
      (node (ref "R32") (pin "1") (pinfunction "1_1") (pintype "passive"))
    )
    (net (code "19") (name "/INPUT-flag01") (class "Default")
      (node (ref "J4") (pin "10") (pinfunction "10_10") (pintype "passive"))
      (node (ref "R30") (pin "2") (pinfunction "2_2") (pintype "passive"))
      (node (ref "U13") (pin "3") (pinfunction "E_3") (pintype "passive"))
    )
    (net (code "20") (name "/INPUT-flag02") (class "Default")
      (node (ref "J4") (pin "11") (pinfunction "11_11") (pintype "passive"))
      (node (ref "R29") (pin "2") (pinfunction "2_2") (pintype "passive"))
      (node (ref "U12") (pin "3") (pinfunction "E_3") (pintype "passive"))
    )
    (net (code "21") (name "/INPUT-flag03") (class "Default")
      (node (ref "J4") (pin "12") (pinfunction "12_12") (pintype "passive"))
      (node (ref "R28") (pin "2") (pinfunction "2_2") (pintype "passive"))
      (node (ref "U11") (pin "3") (pinfunction "E_3") (pintype "passive"))
    )
    (net (code "22") (name "/INPUT-flag04") (class "Default")
      (node (ref "J4") (pin "13") (pinfunction "13_13") (pintype "passive"))
      (node (ref "R27") (pin "2") (pinfunction "2_2") (pintype "passive"))
      (node (ref "U10") (pin "3") (pinfunction "E_3") (pintype "passive"))
    )
    (net (code "23") (name "/INPUT-flag05") (class "Default")
      (node (ref "J4") (pin "14") (pinfunction "14_14") (pintype "passive"))
      (node (ref "R26") (pin "2") (pinfunction "2_2") (pintype "passive"))
      (node (ref "U9") (pin "3") (pinfunction "E_3") (pintype "passive"))
    )
    (net (code "24") (name "/INPUT-flag06") (class "Default")
      (node (ref "J6") (pin "12") (pinfunction "12_12") (pintype "passive"))
      (node (ref "R41") (pin "2") (pinfunction "2_2") (pintype "passive"))
      (node (ref "U15") (pin "3") (pinfunction "E_3") (pintype "passive"))
    )
    (net (code "25") (name "/INPUT-flag07") (class "Default")
      (node (ref "J4") (pin "2") (pinfunction "2_2") (pintype "passive"))
      (node (ref "R40") (pin "2") (pinfunction "2_2") (pintype "passive"))
      (node (ref "U14") (pin "3") (pinfunction "E_3") (pintype "passive"))
    )
    (net (code "27") (name "/OUTPUT00") (class "Default")
      (node (ref "J6") (pin "20") (pinfunction "20_20") (pintype "passive"))
      (node (ref "R14") (pin "1") (pinfunction "1_1") (pintype "passive"))
    )
    (net (code "28") (name "/OUTPUT01") (class "Default")
      (node (ref "J6") (pin "19") (pinfunction "19_19") (pintype "passive"))
      (node (ref "R23") (pin "1") (pinfunction "1_1") (pintype "passive"))
    )
    (net (code "29") (name "/OUTPUT02") (class "Default")
      (node (ref "J6") (pin "18") (pinfunction "18_18") (pintype "passive"))
      (node (ref "R24") (pin "1") (pinfunction "1_1") (pintype "passive"))
    )
    (net (code "30") (name "/OUTPUT03") (class "Default")
      (node (ref "J6") (pin "17") (pinfunction "17_17") (pintype "passive"))
      (node (ref "R25") (pin "1") (pinfunction "1_1") (pintype "passive"))
    )
    (net (code "31") (name "/OUTPUT04") (class "Default")
      (node (ref "J6") (pin "11") (pinfunction "11_11") (pintype "passive"))
      (node (ref "R36") (pin "1") (pinfunction "1_1") (pintype "passive"))
    )
    (net (code "32") (name "/OUTPUT05") (class "Default")
      (node (ref "J6") (pin "5") (pinfunction "5_5") (pintype "passive"))
      (node (ref "R37") (pin "1") (pinfunction "1_1") (pintype "passive"))
    )
    (net (code "33") (name "/OUTPUT06") (class "Default")
      (node (ref "J6") (pin "4") (pinfunction "4_4") (pintype "passive"))
      (node (ref "R38") (pin "1") (pinfunction "1_1") (pintype "passive"))
    )
    (net (code "66") (name "/PR12V") (class "Default")
      (node (ref "C1") (pin "1") (pinfunction "1_1") (pintype "passive"))
      (node (ref "D2") (pin "1") (pinfunction "1_1") (pintype "passive"))
      (node (ref "DB1") (pin "1") (pinfunction "+DC_1") (pintype "passive"))
      (node (ref "J5") (pin "3") (pinfunction "3_3") (pintype "passive"))
      (node (ref "J5") (pin "4") (pinfunction "4_4") (pintype "passive"))
      (node (ref "R9") (pin "1") (pinfunction "1_1") (pintype "passive"))
    )
    (net (code "67") (name "/Power-flag") (class "Default")
      (node (ref "J6") (pin "13") (pinfunction "13_13") (pintype "passive"))
      (node (ref "R11") (pin "1") (pinfunction "1_1") (pintype "passive"))
      (node (ref "U4") (pin "4") (pinfunction "C_4") (pintype "passive"))
    )
    (net (code "68") (name "/RESET") (class "Default")
      (node (ref "J4") (pin "17") (pinfunction "17_17") (pintype "passive"))
    )
    (net (code "69") (name "/RF-R1") (class "Default")
      (node (ref "J6") (pin "9") (pinfunction "9_9") (pintype "passive"))
      (node (ref "U2") (pin "4") (pinfunction "DTA_4") (pintype "passive"))
    )
    (net (code "70") (name "/RF-R2") (class "Default")
      (node (ref "J6") (pin "10") (pinfunction "10_10") (pintype "passive"))
      (node (ref "U6") (pin "4") (pinfunction "DTA_4") (pintype "passive"))
    )
    (net (code "71") (name "/RS485-A") (class "Default")
      (node (ref "J9") (pin "3") (pinfunction "3_3") (pintype "passive"))
      (node (ref "U8") (pin "6") (pinfunction "A_6") (pintype "bidirectional"))
    )
    (net (code "72") (name "/RS485-B") (class "Default")
      (node (ref "J9") (pin "2") (pinfunction "2_2") (pintype "passive"))
      (node (ref "U8") (pin "7") (pinfunction "B_7") (pintype "bidirectional"))
    )
    (net (code "73") (name "/UART-RX-GSM") (class "Default")
      (node (ref "GSM1") (pin "5") (pinfunction "TX_5") (pintype "passive"))
      (node (ref "J4") (pin "16") (pinfunction "16_16") (pintype "passive"))
    )
    (net (code "74") (name "/UART-RX-RS485") (class "Default")
      (node (ref "J6") (pin "14") (pinfunction "14_14") (pintype "passive"))
      (node (ref "J8") (pin "1") (pinfunction "1_1") (pintype "passive"))
      (node (ref "U8") (pin "1") (pinfunction "RO_1") (pintype "output"))
    )
    (net (code "75") (name "/UART-RX-WIFI") (class "Default")
      (node (ref "J4") (pin "7") (pinfunction "7_7") (pintype "passive"))
      (node (ref "U1") (pin "8") (pinfunction "GPIO1_U0TXD_8") (pintype "passive"))
    )
    (net (code "76") (name "/UART-TX-GSM") (class "Default")
      (node (ref "J4") (pin "15") (pinfunction "15_15") (pintype "passive"))
      (node (ref "R2") (pin "1") (pinfunction "1_1") (pintype "passive"))
    )
    (net (code "77") (name "/UART-TX-RS485") (class "Default")
      (node (ref "J6") (pin "15") (pinfunction "15_15") (pintype "passive"))
      (node (ref "J8") (pin "2") (pinfunction "2_2") (pintype "passive"))
      (node (ref "U8") (pin "4") (pinfunction "DI_4") (pintype "input"))
    )
    (net (code "78") (name "/UART-TX-WIFI") (class "Default")
      (node (ref "J4") (pin "8") (pinfunction "8_8") (pintype "passive"))
      (node (ref "U1") (pin "1") (pinfunction "GPIO3_U0RXD_1") (pintype "passive"))
    )
    (net (code "79") (name "/UART-TXEN-RS485") (class "Default")
      (node (ref "J6") (pin "16") (pinfunction "16_16") (pintype "passive"))
      (node (ref "U8") (pin "2") (pinfunction "~{RE}_2") (pintype "input"))
      (node (ref "U8") (pin "3") (pinfunction "DE_3") (pintype "input"))
    )
    (net (code "80") (name "/VBAT") (class "Default")
      (node (ref "J3") (pin "1") (pinfunction "1_1") (pintype "passive"))
      (node (ref "J4") (pin "1") (pinfunction "1_1") (pintype "passive"))
    )
    (net (code "81") (name "/com-Rel0") (class "Default")
      (node (ref "J11") (pin "2") (pinfunction "2_2") (pintype "passive"))
      (node (ref "Rel0") (pin "1") (pinfunction "Com_1") (pintype "power_in"))
    )
    (net (code "82") (name "/com-Rel1") (class "Default")
      (node (ref "J10") (pin "8") (pinfunction "8_8") (pintype "passive"))
      (node (ref "Rel1") (pin "1") (pinfunction "Com_1") (pintype "power_in"))
    )
    (net (code "83") (name "/com-Rel2") (class "Default")
      (node (ref "J10") (pin "5") (pinfunction "5_5") (pintype "passive"))
      (node (ref "Rel2") (pin "1") (pinfunction "Com_1") (pintype "power_in"))
    )
    (net (code "84") (name "/com-Rel3") (class "Default")
      (node (ref "J10") (pin "2") (pinfunction "2_2") (pintype "passive"))
      (node (ref "Rel3") (pin "1") (pinfunction "Com_1") (pintype "power_in"))
    )
    (net (code "85") (name "/com-Rel4") (class "Default")
      (node (ref "J12") (pin "8") (pinfunction "8_8") (pintype "passive"))
      (node (ref "Rel4") (pin "1") (pinfunction "Com_1") (pintype "power_in"))
    )
    (net (code "86") (name "/com-Rel5") (class "Default")
      (node (ref "J12") (pin "5") (pinfunction "5_5") (pintype "passive"))
      (node (ref "Rel5") (pin "1") (pinfunction "Com_1") (pintype "power_in"))
    )
    (net (code "87") (name "/com-Rel6") (class "Default")
      (node (ref "J12") (pin "2") (pinfunction "2_2") (pintype "passive"))
      (node (ref "Rel6") (pin "1") (pinfunction "Com_1") (pintype "power_in"))
    )
    (net (code "88") (name "/nc-Rel0") (class "Default")
      (node (ref "J11") (pin "1") (pinfunction "1_1") (pintype "passive"))
      (node (ref "Rel0") (pin "4") (pinfunction "NC_4") (pintype "power_in"))
    )
    (net (code "89") (name "/nc-Rel1") (class "Default")
      (node (ref "J10") (pin "7") (pinfunction "7_7") (pintype "passive"))
      (node (ref "Rel1") (pin "4") (pinfunction "NC_4") (pintype "power_in"))
    )
    (net (code "90") (name "/nc-Rel2") (class "Default")
      (node (ref "J10") (pin "4") (pinfunction "4_4") (pintype "passive"))
      (node (ref "Rel2") (pin "4") (pinfunction "NC_4") (pintype "power_in"))
    )
    (net (code "91") (name "/nc-Rel3") (class "Default")
      (node (ref "J10") (pin "1") (pinfunction "1_1") (pintype "passive"))
      (node (ref "Rel3") (pin "4") (pinfunction "NC_4") (pintype "power_in"))
    )
    (net (code "92") (name "/nc-Rel4") (class "Default")
      (node (ref "J12") (pin "7") (pinfunction "7_7") (pintype "passive"))
      (node (ref "Rel4") (pin "4") (pinfunction "NC_4") (pintype "power_in"))
    )
    (net (code "93") (name "/nc-Rel5") (class "Default")
      (node (ref "J12") (pin "4") (pinfunction "4_4") (pintype "passive"))
      (node (ref "Rel5") (pin "4") (pinfunction "NC_4") (pintype "power_in"))
    )
    (net (code "94") (name "/nc-Rel6") (class "Default")
      (node (ref "J12") (pin "1") (pinfunction "1_1") (pintype "passive"))
      (node (ref "Rel6") (pin "4") (pinfunction "NC_4") (pintype "power_in"))
    )
    (net (code "95") (name "/no-Rel0") (class "Default")
      (node (ref "J11") (pin "3") (pinfunction "3_3") (pintype "passive"))
      (node (ref "Rel0") (pin "3") (pinfunction "NO_3") (pintype "power_in"))
    )
    (net (code "96") (name "/no-Rel1") (class "Default")
      (node (ref "J10") (pin "9") (pinfunction "9_9") (pintype "passive"))
      (node (ref "Rel1") (pin "3") (pinfunction "NO_3") (pintype "power_in"))
    )
    (net (code "97") (name "/no-Rel2") (class "Default")
      (node (ref "J10") (pin "6") (pinfunction "6_6") (pintype "passive"))
      (node (ref "Rel2") (pin "3") (pinfunction "NO_3") (pintype "power_in"))
    )
    (net (code "98") (name "/no-Rel3") (class "Default")
      (node (ref "J10") (pin "3") (pinfunction "3_3") (pintype "passive"))
      (node (ref "Rel3") (pin "3") (pinfunction "NO_3") (pintype "power_in"))
    )
    (net (code "99") (name "/no-Rel4") (class "Default")
      (node (ref "J12") (pin "9") (pinfunction "9_9") (pintype "passive"))
      (node (ref "Rel4") (pin "3") (pinfunction "NO_3") (pintype "power_in"))
    )
    (net (code "100") (name "/no-Rel5") (class "Default")
      (node (ref "J12") (pin "6") (pinfunction "6_6") (pintype "passive"))
      (node (ref "Rel5") (pin "3") (pinfunction "NO_3") (pintype "power_in"))
    )
    (net (code "101") (name "/no-Rel6") (class "Default")
      (node (ref "J12") (pin "3") (pinfunction "3_3") (pintype "passive"))
      (node (ref "Rel6") (pin "3") (pinfunction "NO_3") (pintype "power_in"))
    )
    (net (code "102") (name "3.3V") (class "Default")
      (node (ref "C5") (pin "2") (pinfunction "2_2") (pintype "passive"))
      (node (ref "J4") (pin "18") (pinfunction "18_18") (pintype "passive"))
      (node (ref "J6") (pin "1") (pinfunction "1_1") (pintype "passive"))
      (node (ref "R11") (pin "2") (pinfunction "2_2") (pintype "passive"))
      (node (ref "U1") (pin "2") (pinfunction "VCC_2") (pintype "passive"))
      (node (ref "U1") (pin "6") (pinfunction "CHIP_PD_6") (pintype "passive"))
      (node (ref "U10") (pin "4") (pinfunction "C_4") (pintype "passive"))
      (node (ref "U11") (pin "4") (pinfunction "C_4") (pintype "passive"))
      (node (ref "U12") (pin "4") (pinfunction "C_4") (pintype "passive"))
      (node (ref "U13") (pin "4") (pinfunction "C_4") (pintype "passive"))
      (node (ref "U14") (pin "4") (pinfunction "C_4") (pintype "passive"))
      (node (ref "U15") (pin "4") (pinfunction "C_4") (pintype "passive"))
      (node (ref "U5") (pin "2") (pinfunction "VO_2") (pintype "passive"))
      (node (ref "U5") (pin "4") (pinfunction "VO_4") (pintype "passive"))
      (node (ref "U7") (pin "8") (pinfunction "VCC_8") (pintype "passive"))
      (node (ref "U9") (pin "4") (pinfunction "C_4") (pintype "passive"))
    )
    (net (code "103") (name "4.2V") (class "Default")
      (node (ref "GSM1") (pin "2") (pinfunction "VCC_2") (pintype "passive"))
      (node (ref "J5") (pin "7") (pinfunction "7_7") (pintype "passive"))
      (node (ref "R42") (pin "2") (pinfunction "2_2") (pintype "passive"))
    )
    (net (code "104") (name "5V") (class "Default")
      (node (ref "C3") (pin "2") (pinfunction "2_2") (pintype "passive"))
      (node (ref "R10") (pin "2") (pinfunction "2_2") (pintype "passive"))
      (node (ref "R12") (pin "2") (pinfunction "2_2") (pintype "passive"))
      (node (ref "U2") (pin "3") (pinfunction "VCC_3") (pintype "passive"))
      (node (ref "U3") (pin "2") (pinfunction "VO_2") (pintype "passive"))
      (node (ref "U3") (pin "4") (pinfunction "VO_4") (pintype "passive"))
      (node (ref "U6") (pin "3") (pinfunction "VCC_3") (pintype "passive"))
    )
    (net (code "105") (name "5VRS485") (class "Default")
      (node (ref "C14") (pin "2") (pinfunction "2_2") (pintype "passive"))
      (node (ref "R42") (pin "1") (pinfunction "1_1") (pintype "passive"))
      (node (ref "U16") (pin "2") (pinfunction "VO_2") (pintype "passive"))
      (node (ref "U16") (pin "4") (pinfunction "VO_4") (pintype "passive"))
      (node (ref "U8") (pin "8") (pinfunction "V_8") (pintype "passive"))
    )
    (net (code "106") (name "12V") (class "Default")
      (node (ref "C13") (pin "2") (pinfunction "2_2") (pintype "passive"))
      (node (ref "C2") (pin "2") (pinfunction "2_2") (pintype "passive"))
      (node (ref "C4") (pin "2") (pinfunction "2_2") (pintype "passive"))
      (node (ref "D12") (pin "1") (pinfunction "A_1") (pintype "passive"))
      (node (ref "D13") (pin "1") (pinfunction "A_1") (pintype "passive"))
      (node (ref "D14") (pin "1") (pinfunction "A_1") (pintype "passive"))
      (node (ref "D15") (pin "2") (pinfunction "2_2") (pintype "passive"))
      (node (ref "D16") (pin "2") (pinfunction "2_2") (pintype "passive"))
      (node (ref "D17") (pin "2") (pinfunction "2_2") (pintype "passive"))
      (node (ref "D2") (pin "2") (pinfunction "2_2") (pintype "passive"))
      (node (ref "D20") (pin "1") (pinfunction "A_1") (pintype "passive"))
      (node (ref "D21") (pin "1") (pinfunction "A_1") (pintype "passive"))
      (node (ref "D22") (pin "1") (pinfunction "A_1") (pintype "passive"))
      (node (ref "D23") (pin "2") (pinfunction "2_2") (pintype "passive"))
      (node (ref "D24") (pin "2") (pinfunction "2_2") (pintype "passive"))
      (node (ref "D25") (pin "2") (pinfunction "2_2") (pintype "passive"))
      (node (ref "D5") (pin "1") (pinfunction "A_1") (pintype "passive"))
      (node (ref "D6") (pin "2") (pinfunction "2_2") (pintype "passive"))
      (node (ref "J13") (pin "3") (pinfunction "3_3") (pintype "passive"))
      (node (ref "J2") (pin "1") (pinfunction "1_1") (pintype "passive"))
      (node (ref "J2") (pin "3") (pinfunction "3_3") (pintype "passive"))
      (node (ref "J2") (pin "5") (pinfunction "5_5") (pintype "passive"))
      (node (ref "J5") (pin "1") (pinfunction "1_1") (pintype "passive"))
      (node (ref "J5") (pin "2") (pinfunction "2_2") (pintype "passive"))
      (node (ref "J9") (pin "1") (pinfunction "1_1") (pintype "passive"))
      (node (ref "Rel0") (pin "2") (pinfunction "Coli1_2") (pintype "power_in"))
      (node (ref "Rel1") (pin "2") (pinfunction "Coli1_2") (pintype "power_in"))
      (node (ref "Rel2") (pin "2") (pinfunction "Coli1_2") (pintype "power_in"))
      (node (ref "Rel3") (pin "2") (pinfunction "Coli1_2") (pintype "power_in"))
      (node (ref "Rel4") (pin "2") (pinfunction "Coli1_2") (pintype "power_in"))
      (node (ref "Rel5") (pin "2") (pinfunction "Coli1_2") (pintype "power_in"))
      (node (ref "Rel6") (pin "2") (pinfunction "Coli1_2") (pintype "power_in"))
      (node (ref "U16") (pin "3") (pinfunction "VIN_3") (pintype "passive"))
      (node (ref "U3") (pin "3") (pinfunction "VIN_3") (pintype "passive"))
      (node (ref "U5") (pin "3") (pinfunction "VIN_3") (pintype "passive"))
    )
    (net (code "107") (name "GND") (class "Default")
      (node (ref "C1") (pin "2") (pinfunction "2_2") (pintype "passive"))
      (node (ref "C13") (pin "1") (pinfunction "1_1") (pintype "passive"))
      (node (ref "C14") (pin "1") (pinfunction "1_1") (pintype "passive"))
      (node (ref "C2") (pin "1") (pinfunction "1_1") (pintype "passive"))
      (node (ref "C3") (pin "1") (pinfunction "1_1") (pintype "passive"))
      (node (ref "C4") (pin "1") (pinfunction "1_1") (pintype "passive"))
      (node (ref "C5") (pin "1") (pinfunction "1_1") (pintype "passive"))
      (node (ref "D1") (pin "1") (pinfunction "1_1") (pintype "passive"))
      (node (ref "D3") (pin "1") (pinfunction "1_1") (pintype "passive"))
      (node (ref "D4") (pin "1") (pinfunction "1_1") (pintype "passive"))
      (node (ref "DB1") (pin "3") (pinfunction "-DC_3") (pintype "passive"))
      (node (ref "GSM1") (pin "6") (pinfunction "GND_6") (pintype "passive"))
      (node (ref "J2") (pin "7") (pinfunction "7_7") (pintype "passive"))
      (node (ref "J3") (pin "2") (pinfunction "2_2") (pintype "passive"))
      (node (ref "J4") (pin "19") (pinfunction "19_19") (pintype "passive"))
      (node (ref "J4") (pin "20") (pinfunction "20_20") (pintype "passive"))
      (node (ref "J5") (pin "5") (pinfunction "5_5") (pintype "passive"))
      (node (ref "J5") (pin "6") (pinfunction "6_6") (pintype "passive"))
      (node (ref "J6") (pin "2") (pinfunction "2_2") (pintype "passive"))
      (node (ref "J8") (pin "3") (pinfunction "3_3") (pintype "passive"))
      (node (ref "J9") (pin "4") (pinfunction "4_4") (pintype "passive"))
      (node (ref "Q1") (pin "1") (pinfunction "E_1") (pintype "passive"))
      (node (ref "Q2") (pin "1") (pinfunction "E_1") (pintype "passive"))
      (node (ref "Q3") (pin "1") (pinfunction "E_1") (pintype "passive"))
      (node (ref "Q4") (pin "1") (pinfunction "E_1") (pintype "passive"))
      (node (ref "Q5") (pin "1") (pinfunction "E_1") (pintype "passive"))
      (node (ref "Q6") (pin "1") (pinfunction "E_1") (pintype "passive"))
      (node (ref "Q7") (pin "1") (pinfunction "E_1") (pintype "passive"))
      (node (ref "R1") (pin "2") (pinfunction "2_2") (pintype "passive"))
      (node (ref "R26") (pin "1") (pinfunction "1_1") (pintype "passive"))
      (node (ref "R27") (pin "1") (pinfunction "1_1") (pintype "passive"))
      (node (ref "R28") (pin "1") (pinfunction "1_1") (pintype "passive"))
      (node (ref "R29") (pin "1") (pinfunction "1_1") (pintype "passive"))
      (node (ref "R30") (pin "1") (pinfunction "1_1") (pintype "passive"))
      (node (ref "R39") (pin "2") (pinfunction "2_2") (pintype "passive"))
      (node (ref "R4") (pin "2") (pinfunction "2_2") (pintype "passive"))
      (node (ref "R40") (pin "1") (pinfunction "1_1") (pintype "passive"))
      (node (ref "R41") (pin "1") (pinfunction "1_1") (pintype "passive"))
      (node (ref "R6") (pin "2") (pinfunction "2_2") (pintype "passive"))
      (node (ref "R8") (pin "2") (pinfunction "2_2") (pintype "passive"))
      (node (ref "U1") (pin "7") (pinfunction "GND_7") (pintype "passive"))
      (node (ref "U16") (pin "1") (pinfunction "GND_1") (pintype "passive"))
      (node (ref "U2") (pin "2") (pinfunction "GND_2") (pintype "passive"))
      (node (ref "U2") (pin "6") (pinfunction "GND_6") (pintype "passive"))
      (node (ref "U3") (pin "1") (pinfunction "GND_1") (pintype "passive"))
      (node (ref "U4") (pin "2") (pinfunction "K_2") (pintype "passive"))
      (node (ref "U4") (pin "3") (pinfunction "E_3") (pintype "passive"))
      (node (ref "U5") (pin "1") (pinfunction "GND_1") (pintype "passive"))
      (node (ref "U6") (pin "2") (pinfunction "GND_2") (pintype "passive"))
      (node (ref "U6") (pin "6") (pinfunction "GND_6") (pintype "passive"))
      (node (ref "U7") (pin "4") (pinfunction "GND_4") (pintype "passive"))
      (node (ref "U8") (pin "5") (pinfunction "G_5") (pintype "passive"))
    )
    (net (code "108") (name "Net-(D5-K)") (class "Default")
      (node (ref "D5") (pin "2") (pinfunction "K_2") (pintype "passive"))
      (node (ref "R13") (pin "2") (pinfunction "2_2") (pintype "passive"))
    )
    (net (code "109") (name "Net-(D7-Pad1)") (class "Default")
      (node (ref "D7") (pin "1") (pinfunction "1_1") (pintype "passive"))
      (node (ref "R15") (pin "2") (pinfunction "2_2") (pintype "passive"))
    )
    (net (code "110") (name "Net-(D8-Pad1)") (class "Default")
      (node (ref "D8") (pin "1") (pinfunction "1_1") (pintype "passive"))
      (node (ref "R16") (pin "2") (pinfunction "2_2") (pintype "passive"))
    )
    (net (code "111") (name "Net-(D9-Pad1)") (class "Default")
      (node (ref "D9") (pin "1") (pinfunction "1_1") (pintype "passive"))
      (node (ref "R17") (pin "2") (pinfunction "2_2") (pintype "passive"))
    )
    (net (code "112") (name "Net-(D10-Pad1)") (class "Default")
      (node (ref "D10") (pin "1") (pinfunction "1_1") (pintype "passive"))
      (node (ref "R18") (pin "2") (pinfunction "2_2") (pintype "passive"))
    )
    (net (code "113") (name "Net-(D11-Pad1)") (class "Default")
      (node (ref "D11") (pin "1") (pinfunction "1_1") (pintype "passive"))
      (node (ref "R19") (pin "2") (pinfunction "2_2") (pintype "passive"))
    )
    (net (code "114") (name "Net-(D12-K)") (class "Default")
      (node (ref "D12") (pin "2") (pinfunction "K_2") (pintype "passive"))
      (node (ref "R20") (pin "2") (pinfunction "2_2") (pintype "passive"))
    )
    (net (code "115") (name "Net-(D13-K)") (class "Default")
      (node (ref "D13") (pin "2") (pinfunction "K_2") (pintype "passive"))
      (node (ref "R21") (pin "2") (pinfunction "2_2") (pintype "passive"))
    )
    (net (code "116") (name "Net-(D14-K)") (class "Default")
      (node (ref "D14") (pin "2") (pinfunction "K_2") (pintype "passive"))
      (node (ref "R22") (pin "2") (pinfunction "2_2") (pintype "passive"))
    )
    (net (code "117") (name "Net-(D18-Pad1)") (class "Default")
      (node (ref "D18") (pin "1") (pinfunction "1_1") (pintype "passive"))
      (node (ref "R31") (pin "2") (pinfunction "2_2") (pintype "passive"))
    )
    (net (code "118") (name "Net-(D19-Pad1)") (class "Default")
      (node (ref "D19") (pin "1") (pinfunction "1_1") (pintype "passive"))
      (node (ref "R32") (pin "2") (pinfunction "2_2") (pintype "passive"))
    )
    (net (code "119") (name "Net-(D20-K)") (class "Default")
      (node (ref "D20") (pin "2") (pinfunction "K_2") (pintype "passive"))
      (node (ref "R33") (pin "2") (pinfunction "2_2") (pintype "passive"))
    )
    (net (code "120") (name "Net-(D21-K)") (class "Default")
      (node (ref "D21") (pin "2") (pinfunction "K_2") (pintype "passive"))
      (node (ref "R34") (pin "2") (pinfunction "2_2") (pintype "passive"))
    )
    (net (code "121") (name "Net-(D22-K)") (class "Default")
      (node (ref "D22") (pin "2") (pinfunction "K_2") (pintype "passive"))
      (node (ref "R35") (pin "2") (pinfunction "2_2") (pintype "passive"))
    )
    (net (code "122") (name "Net-(GSM1-MICN)") (class "Default")
      (node (ref "GSM1") (pin "10") (pinfunction "MICN_10") (pintype "passive"))
      (node (ref "J7") (pin "2") (pinfunction "2_2") (pintype "passive"))
    )
    (net (code "123") (name "Net-(GSM1-MICP)") (class "Default")
      (node (ref "GSM1") (pin "9") (pinfunction "MICP_9") (pintype "passive"))
      (node (ref "J7") (pin "1") (pinfunction "1_1") (pintype "passive"))
    )
    (net (code "124") (name "Net-(GSM1-RX)") (class "Default")
      (node (ref "GSM1") (pin "4") (pinfunction "RX_4") (pintype "passive"))
      (node (ref "R1") (pin "1") (pinfunction "1_1") (pintype "passive"))
      (node (ref "R2") (pin "2") (pinfunction "2_2") (pintype "passive"))
    )
    (net (code "125") (name "Net-(GSM1-SPKN)") (class "Default")
      (node (ref "GSM1") (pin "12") (pinfunction "SPKN_12") (pintype "passive"))
      (node (ref "J7") (pin "4") (pinfunction "4_4") (pintype "passive"))
    )
    (net (code "126") (name "Net-(GSM1-SPKP)") (class "Default")
      (node (ref "GSM1") (pin "11") (pinfunction "SPKP_11") (pintype "passive"))
      (node (ref "J7") (pin "3") (pinfunction "3_3") (pintype "passive"))
    )
    (net (code "127") (name "Net-(J2-Pad2)") (class "Default")
      (node (ref "J2") (pin "2") (pinfunction "2_2") (pintype "passive"))
      (node (ref "R3") (pin "1") (pinfunction "1_1") (pintype "passive"))
    )
    (net (code "128") (name "Net-(J2-Pad4)") (class "Default")
      (node (ref "J2") (pin "4") (pinfunction "4_4") (pintype "passive"))
      (node (ref "R5") (pin "1") (pinfunction "1_1") (pintype "passive"))
    )
    (net (code "129") (name "Net-(J2-Pad6)") (class "Default")
      (node (ref "J2") (pin "6") (pinfunction "6_6") (pintype "passive"))
      (node (ref "R7") (pin "1") (pinfunction "1_1") (pintype "passive"))
    )
    (net (code "130") (name "Net-(Q1-B)") (class "Default")
      (node (ref "Q1") (pin "3") (pinfunction "B_3") (pintype "passive"))
      (node (ref "R14") (pin "2") (pinfunction "2_2") (pintype "passive"))
    )
    (net (code "131") (name "Net-(Q1-C)") (class "Default")
      (node (ref "D6") (pin "1") (pinfunction "1_1") (pintype "passive"))
      (node (ref "Q1") (pin "2") (pinfunction "C_2") (pintype "passive"))
      (node (ref "R13") (pin "1") (pinfunction "1_1") (pintype "passive"))
      (node (ref "Rel0") (pin "5") (pinfunction "Coli2_5") (pintype "power_in"))
    )
    (net (code "132") (name "Net-(Q2-B)") (class "Default")
      (node (ref "Q2") (pin "3") (pinfunction "B_3") (pintype "passive"))
      (node (ref "R23") (pin "2") (pinfunction "2_2") (pintype "passive"))
    )
    (net (code "133") (name "Net-(Q2-C)") (class "Default")
      (node (ref "D15") (pin "1") (pinfunction "1_1") (pintype "passive"))
      (node (ref "Q2") (pin "2") (pinfunction "C_2") (pintype "passive"))
      (node (ref "R20") (pin "1") (pinfunction "1_1") (pintype "passive"))
      (node (ref "Rel1") (pin "5") (pinfunction "Coli2_5") (pintype "power_in"))
    )
    (net (code "134") (name "Net-(Q3-B)") (class "Default")
      (node (ref "Q3") (pin "3") (pinfunction "B_3") (pintype "passive"))
      (node (ref "R24") (pin "2") (pinfunction "2_2") (pintype "passive"))
    )
    (net (code "135") (name "Net-(Q3-C)") (class "Default")
      (node (ref "D16") (pin "1") (pinfunction "1_1") (pintype "passive"))
      (node (ref "Q3") (pin "2") (pinfunction "C_2") (pintype "passive"))
      (node (ref "R21") (pin "1") (pinfunction "1_1") (pintype "passive"))
      (node (ref "Rel2") (pin "5") (pinfunction "Coli2_5") (pintype "power_in"))
    )
    (net (code "136") (name "Net-(Q4-B)") (class "Default")
      (node (ref "Q4") (pin "3") (pinfunction "B_3") (pintype "passive"))
      (node (ref "R25") (pin "2") (pinfunction "2_2") (pintype "passive"))
    )
    (net (code "137") (name "Net-(Q4-C)") (class "Default")
      (node (ref "D17") (pin "1") (pinfunction "1_1") (pintype "passive"))
      (node (ref "Q4") (pin "2") (pinfunction "C_2") (pintype "passive"))
      (node (ref "R22") (pin "1") (pinfunction "1_1") (pintype "passive"))
      (node (ref "Rel3") (pin "5") (pinfunction "Coli2_5") (pintype "power_in"))
    )
    (net (code "138") (name "Net-(Q5-B)") (class "Default")
      (node (ref "Q5") (pin "3") (pinfunction "B_3") (pintype "passive"))
      (node (ref "R36") (pin "2") (pinfunction "2_2") (pintype "passive"))
    )
    (net (code "139") (name "Net-(Q5-C)") (class "Default")
      (node (ref "D23") (pin "1") (pinfunction "1_1") (pintype "passive"))
      (node (ref "Q5") (pin "2") (pinfunction "C_2") (pintype "passive"))
      (node (ref "R33") (pin "1") (pinfunction "1_1") (pintype "passive"))
      (node (ref "Rel4") (pin "5") (pinfunction "Coli2_5") (pintype "power_in"))
    )
    (net (code "140") (name "Net-(Q6-B)") (class "Default")
      (node (ref "Q6") (pin "3") (pinfunction "B_3") (pintype "passive"))
      (node (ref "R37") (pin "2") (pinfunction "2_2") (pintype "passive"))
    )
    (net (code "141") (name "Net-(Q6-C)") (class "Default")
      (node (ref "D24") (pin "1") (pinfunction "1_1") (pintype "passive"))
      (node (ref "Q6") (pin "2") (pinfunction "C_2") (pintype "passive"))
      (node (ref "R34") (pin "1") (pinfunction "1_1") (pintype "passive"))
      (node (ref "Rel5") (pin "5") (pinfunction "Coli2_5") (pintype "power_in"))
    )
    (net (code "142") (name "Net-(Q7-B)") (class "Default")
      (node (ref "Q7") (pin "3") (pinfunction "B_3") (pintype "passive"))
      (node (ref "R38") (pin "2") (pinfunction "2_2") (pintype "passive"))
    )
    (net (code "143") (name "Net-(Q7-C)") (class "Default")
      (node (ref "D25") (pin "1") (pinfunction "1_1") (pintype "passive"))
      (node (ref "Q7") (pin "2") (pinfunction "C_2") (pintype "passive"))
      (node (ref "R35") (pin "1") (pinfunction "1_1") (pintype "passive"))
      (node (ref "Rel6") (pin "5") (pinfunction "Coli2_5") (pintype "power_in"))
    )
    (net (code "144") (name "Net-(R10-Pad1)") (class "Default")
      (node (ref "R10") (pin "1") (pinfunction "1_1") (pintype "passive"))
      (node (ref "U2") (pin "5") (pinfunction "DTA_5") (pintype "passive"))
    )
    (net (code "145") (name "Net-(R12-Pad1)") (class "Default")
      (node (ref "R12") (pin "1") (pinfunction "1_1") (pintype "passive"))
      (node (ref "U6") (pin "5") (pinfunction "DTA_5") (pintype "passive"))
    )
    (net (code "146") (name "Net-(U4-A)") (class "Default")
      (node (ref "R9") (pin "2") (pinfunction "2_2") (pintype "passive"))
      (node (ref "U4") (pin "1") (pinfunction "A_1") (pintype "passive"))
    )
    (net (code "147") (name "Net-(U9-A)") (class "Default")
      (node (ref "C6") (pin "1") (pinfunction "1_1") (pintype "passive"))
      (node (ref "D7") (pin "2") (pinfunction "2_2") (pintype "passive"))
      (node (ref "U9") (pin "1") (pinfunction "A_1") (pintype "passive"))
    )
    (net (code "148") (name "Net-(U10-A)") (class "Default")
      (node (ref "C7") (pin "1") (pinfunction "1_1") (pintype "passive"))
      (node (ref "D8") (pin "2") (pinfunction "2_2") (pintype "passive"))
      (node (ref "U10") (pin "1") (pinfunction "A_1") (pintype "passive"))
    )
    (net (code "149") (name "Net-(U11-A)") (class "Default")
      (node (ref "C8") (pin "1") (pinfunction "1_1") (pintype "passive"))
      (node (ref "D9") (pin "2") (pinfunction "2_2") (pintype "passive"))
      (node (ref "U11") (pin "1") (pinfunction "A_1") (pintype "passive"))
    )
    (net (code "150") (name "Net-(U12-A)") (class "Default")
      (node (ref "C9") (pin "1") (pinfunction "1_1") (pintype "passive"))
      (node (ref "D10") (pin "2") (pinfunction "2_2") (pintype "passive"))
      (node (ref "U12") (pin "1") (pinfunction "A_1") (pintype "passive"))
    )
    (net (code "151") (name "Net-(U13-A)") (class "Default")
      (node (ref "C10") (pin "1") (pinfunction "1_1") (pintype "passive"))
      (node (ref "D11") (pin "2") (pinfunction "2_2") (pintype "passive"))
      (node (ref "U13") (pin "1") (pinfunction "A_1") (pintype "passive"))
    )
    (net (code "152") (name "Net-(U14-A)") (class "Default")
      (node (ref "C11") (pin "1") (pinfunction "1_1") (pintype "passive"))
      (node (ref "D18") (pin "2") (pinfunction "2_2") (pintype "passive"))
      (node (ref "U14") (pin "1") (pinfunction "A_1") (pintype "passive"))
    )
    (net (code "153") (name "Net-(U15-A)") (class "Default")
      (node (ref "C12") (pin "1") (pinfunction "1_1") (pintype "passive"))
      (node (ref "D19") (pin "2") (pinfunction "2_2") (pintype "passive"))
      (node (ref "U15") (pin "1") (pinfunction "A_1") (pintype "passive"))
    )
    (net (code "154") (name "unconnected-(GSM1-DRT-Pad8)") (class "Default")
      (node (ref "GSM1") (pin "8") (pinfunction "DRT_8") (pintype "passive"))
    )
    (net (code "155") (name "unconnected-(GSM1-RING-Pad7)") (class "Default")
      (node (ref "GSM1") (pin "7") (pinfunction "RING_7") (pintype "passive"))
    )
    (net (code "156") (name "unconnected-(GSM1-RST-Pad3)") (class "Default")
      (node (ref "GSM1") (pin "3") (pinfunction "RST_3") (pintype "passive"))
    )
    (net (code "157") (name "unconnected-(J4-Pad3)") (class "Default")
      (node (ref "J4") (pin "3") (pinfunction "3_3") (pintype "passive"))
    )
    (net (code "158") (name "unconnected-(J4-Pad4)") (class "Default")
      (node (ref "J4") (pin "4") (pinfunction "4_4") (pintype "passive"))
    )
    (net (code "159") (name "unconnected-(J6-Pad3)") (class "Default")
      (node (ref "J6") (pin "3") (pinfunction "3_3") (pintype "passive"))
    )
    (net (code "160") (name "unconnected-(U1-GPIO0-Pad3)") (class "Default")
      (node (ref "U1") (pin "3") (pinfunction "GPIO0_3") (pintype "passive"))
    )
    (net (code "161") (name "unconnected-(U1-GPIO2_U1TXD-Pad5)") (class "Default")
      (node (ref "U1") (pin "5") (pinfunction "GPIO2_U1TXD_5") (pintype "passive"))
    )
    (net (code "162") (name "unconnected-(U1-RESET#-Pad4)") (class "Default")
      (node (ref "U1") (pin "4") (pinfunction "RESET#_4") (pintype "passive"))
    )
    (net (code "163") (name "unconnected-(U2-ANT-Pad1)") (class "Default")
      (node (ref "U2") (pin "1") (pinfunction "ANT_1") (pintype "passive"))
    )
    (net (code "164") (name "unconnected-(U6-ANT-Pad1)") (class "Default")
      (node (ref "U6") (pin "1") (pinfunction "ANT_1") (pintype "passive"))
    )
    (net (code "165") (name "unconnected-(U7-A0-Pad1)") (class "Default")
      (node (ref "U7") (pin "1") (pinfunction "A0_1") (pintype "passive"))
    )
    (net (code "166") (name "unconnected-(U7-A1-Pad2)") (class "Default")
      (node (ref "U7") (pin "2") (pinfunction "A1_2") (pintype "passive"))
    )
    (net (code "167") (name "unconnected-(U7-A2-Pad3)") (class "Default")
      (node (ref "U7") (pin "3") (pinfunction "A2_3") (pintype "passive"))
    )
  )
)
